# BT832A.net
KiCad netlist of a schematic drawn in EAGLE
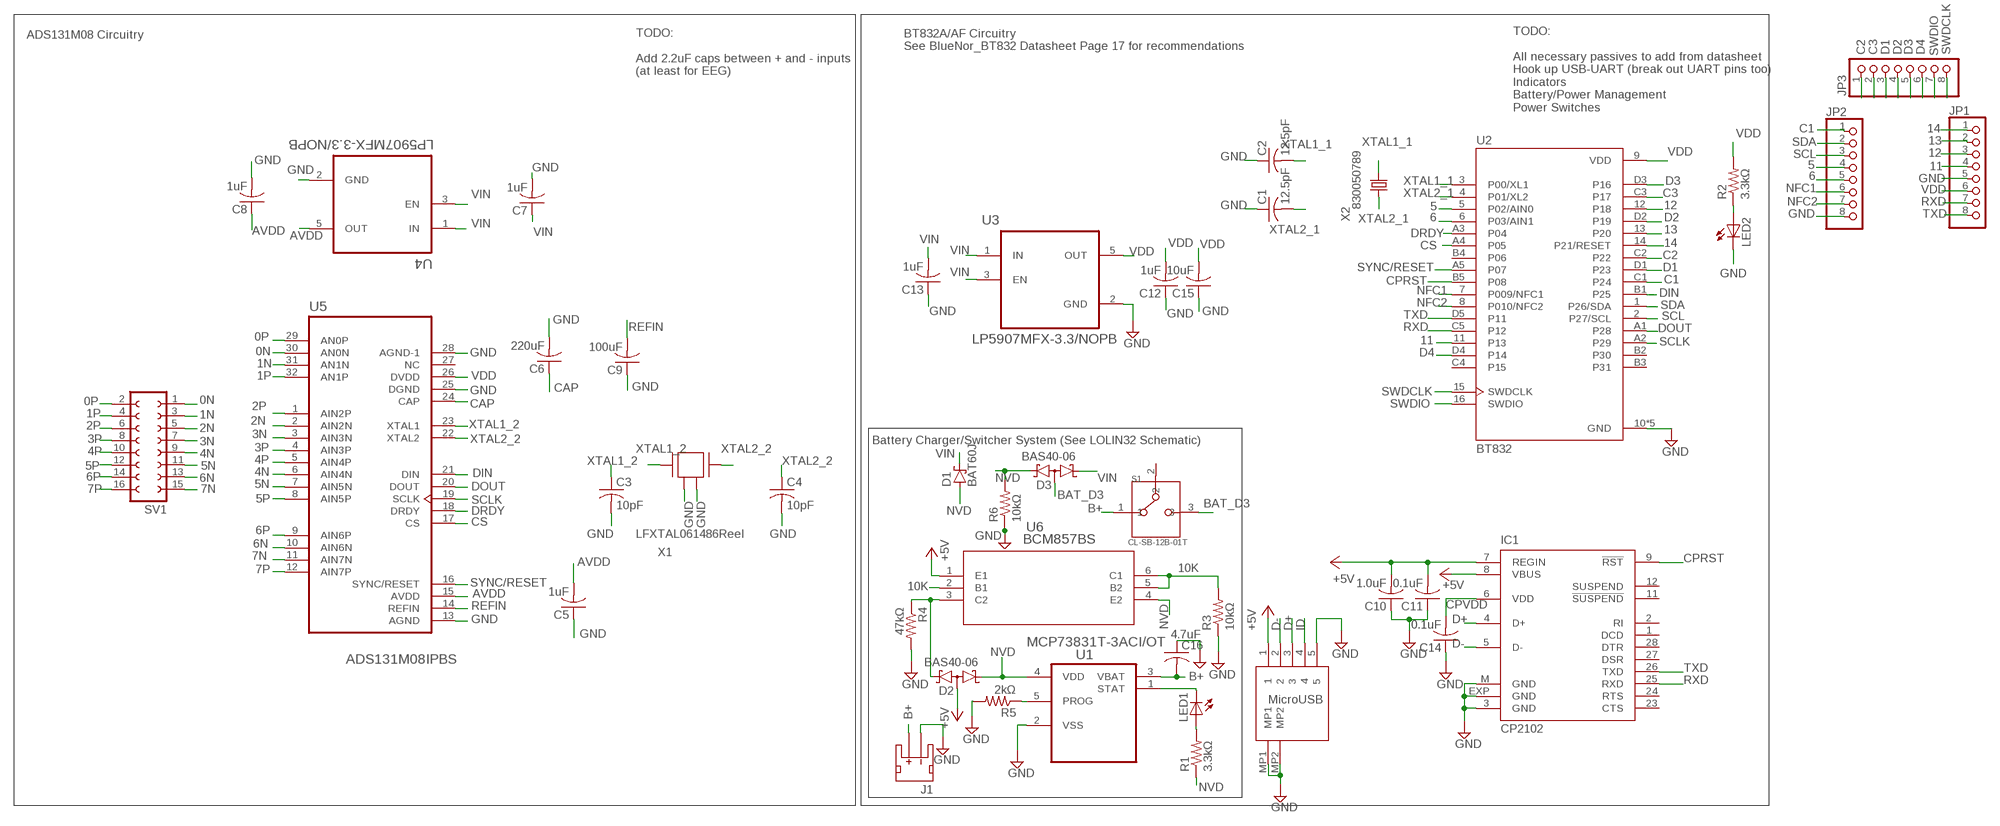
[diagram p0: schematic, sheet 1]

(export (version "E")
  (design (tool "Eeschema 10.0.6"))
  (components
    (comp (ref "C1")
      (value "12.5pF")
      (footprint "eagle-import:C0402")
      (libsource (lib "eagle-import") (part "adafruit_420_C-USC0402"))
    )
    (comp (ref "C2")
      (value "12.5pF")
      (footprint "eagle-import:C0402")
      (libsource (lib "eagle-import") (part "adafruit_420_C-USC0402"))
    )
    (comp (ref "C3")
      (value "10pF")
      (footprint "eagle-import:C0402")
      (libsource (lib "eagle-import") (part "adafruit_420_C-USC0402"))
    )
    (comp (ref "C4")
      (value "10pF")
      (footprint "eagle-import:C0402")
      (libsource (lib "eagle-import") (part "adafruit_420_C-USC0402"))
    )
    (comp (ref "C5")
      (value "1uF")
      (footprint "eagle-import:C0402")
      (libsource (lib "eagle-import") (part "C-USC0402"))
    )
    (comp (ref "C6")
      (value "220uF")
      (footprint "eagle-import:C0402")
      (libsource (lib "eagle-import") (part "C-USC0402"))
    )
    (comp (ref "C7")
      (value "1uF")
      (footprint "eagle-import:C0402")
      (libsource (lib "eagle-import") (part "C-USC0402"))
    )
    (comp (ref "C8")
      (value "1uF")
      (footprint "eagle-import:C0402")
      (libsource (lib "eagle-import") (part "C-USC0402"))
    )
    (comp (ref "C9")
      (value "100uF")
      (footprint "eagle-import:C0402")
      (libsource (lib "eagle-import") (part "C-USC0402"))
    )
    (comp (ref "C10")
      (value "1.0uF")
      (footprint "eagle-import:C0402")
      (libsource (lib "eagle-import") (part "adafruit_420_C-USC0402"))
    )
    (comp (ref "C11")
      (value "0.1uF")
      (footprint "eagle-import:C0402")
      (libsource (lib "eagle-import") (part "adafruit_420_C-USC0402"))
    )
    (comp (ref "C12")
      (value "1uF")
      (footprint "eagle-import:C0402")
      (libsource (lib "eagle-import") (part "C-USC0402"))
    )
    (comp (ref "C13")
      (value "1uF")
      (footprint "eagle-import:C0402")
      (libsource (lib "eagle-import") (part "C-USC0402"))
    )
    (comp (ref "C14")
      (value "0.1uF")
      (footprint "eagle-import:C0402")
      (libsource (lib "eagle-import") (part "adafruit_420_C-USC0402"))
    )
    (comp (ref "C15")
      (value "10uF")
      (footprint "eagle-import:C0402")
      (libsource (lib "eagle-import") (part "C-USC0402"))
    )
    (comp (ref "C16")
      (value "4.7uF")
      (footprint "eagle-import:C0402")
      (libsource (lib "eagle-import") (part "adafruit_420_C-USC0402"))
    )
    (comp (ref "D1")
      (value "BAT60J")
      (footprint "eagle-import:SOD323_ST")
      (libsource (lib "eagle-import") (part "BAT60J"))
    )
    (comp (ref "D2")
      (value "BAS40-06")
      (footprint "eagle-import:SOT23")
      (libsource (lib "eagle-import") (part "BAS40-06"))
    )
    (comp (ref "D3")
      (value "BAS40-06")
      (footprint "eagle-import:SOT23")
      (libsource (lib "eagle-import") (part "BAS40-06"))
    )
    (comp (ref "IC1")
      (value "CP2102")
      (footprint "eagle-import:MLP28")
      (fields (field (name "MF") "FARNELL") (field (name "MPN") "CP2102-GM"))
      (libsource (lib "eagle-import") (part "CP2102"))
    )
    (comp (ref "J1")
      (value "JST_2MM_MALE")
      (footprint "eagle-import:JST-2-SMD")
      (libsource (lib "eagle-import") (part "JST_2MM_MALE"))
    )
    (comp (ref "JP1")
      (value "PINHD-1X8CLEANBIG")
      (footprint "eagle-import:1X08-CLEANBIG")
      (libsource (lib "eagle-import") (part "PINHD-1X8CLEANBIG"))
    )
    (comp (ref "JP2")
      (value "PINHD-1X8CLEANBIG")
      (footprint "eagle-import:1X08-CLEANBIG")
      (libsource (lib "eagle-import") (part "PINHD-1X8CLEANBIG"))
    )
    (comp (ref "JP3")
      (value "PINHD-1X8CLEANBIG")
      (footprint "eagle-import:1X08-CLEANBIG")
      (libsource (lib "eagle-import") (part "PINHD-1X8CLEANBIG"))
    )
    (comp (ref "LED1")
      (value "LEDCHIP-LED0603")
      (footprint "eagle-import:CHIP-LED0603")
      (libsource (lib "eagle-import") (part "LEDCHIP-LED0603"))
    )
    (comp (ref "LED2")
      (value "LEDCHIP-LED0603")
      (footprint "eagle-import:CHIP-LED0603")
      (libsource (lib "eagle-import") (part "LEDCHIP-LED0603"))
    )
    (comp (ref "R1")
      (value "3.3kΩ")
      (footprint "eagle-import:R0402")
      (libsource (lib "eagle-import") (part "R-US_R0402"))
    )
    (comp (ref "R2")
      (value "3.3kΩ")
      (footprint "eagle-import:R0402")
      (libsource (lib "eagle-import") (part "R-US_R0402"))
    )
    (comp (ref "R3")
      (value "10kΩ")
      (footprint "eagle-import:R0402")
      (libsource (lib "eagle-import") (part "R-US_R0402"))
    )
    (comp (ref "R4")
      (value "47kΩ")
      (footprint "eagle-import:R0402")
      (libsource (lib "eagle-import") (part "R-US_R0402"))
    )
    (comp (ref "R5")
      (value "2kΩ")
      (footprint "eagle-import:R0402")
      (libsource (lib "eagle-import") (part "R-US_R0402"))
    )
    (comp (ref "R6")
      (value "10kΩ")
      (footprint "eagle-import:R0402")
      (libsource (lib "eagle-import") (part "R-US_R0402"))
    )
    (comp (ref "S1")
      (value "CL-SB-12B-01T")
      (footprint "eagle-import:CL-SB-12B")
      (fields (field (name "MF") "Nidec Copal"))
      (libsource (lib "eagle-import") (part "CL-SB-12B-01T"))
    )
    (comp (ref "SV1")
      (value "FE08-2")
      (footprint "eagle-import:FE08-2")
      (libsource (lib "eagle-import") (part "FE08-2"))
    )
    (comp (ref "U$1")
      (value "DX4R005JJ2R1800")
      (footprint "eagle-import:DX4R005JJ2R1800")
      (fields (field (name "MF") "JAE Electronics"))
      (libsource (lib "eagle-import") (part "DX4R005JJ2R1800"))
    )
    (comp (ref "U1")
      (value "MCP73831T-3ACI/OT")
      (footprint "eagle-import:SOT95P270X145-5N")
      (fields (field (name "MF") "Microchip"))
      (libsource (lib "eagle-import") (part "MCP73831T-3ACI/OT"))
    )
    (comp (ref "U2")
      (value "BT832")
      (footprint "eagle-import:BLEMODULE_BT832")
      (fields (field (name "MF") "Fanstel Corp."))
      (libsource (lib "eagle-import") (part "BT832"))
    )
    (comp (ref "U3")
      (value "LP5907MFX-3.3/NOPB")
      (footprint "eagle-import:SOT95P280X145-5N")
      (fields (field (name "MF") "Texas Instruments"))
      (libsource (lib "eagle-import") (part "LP5907MFX-3.3/NOPB"))
    )
    (comp (ref "U4")
      (value "LP5907MFX-3.3/NOPB")
      (footprint "eagle-import:SOT95P280X145-5N")
      (fields (field (name "MF") "Texas Instruments"))
      (libsource (lib "eagle-import") (part "LP5907MFX-3.3/NOPB"))
    )
    (comp (ref "U5")
      (value "ADS131M08IPBS")
      (footprint "eagle-import:QFP50P700X700X120-32N")
      (fields (field (name "MF") "Texas Instruments"))
      (libsource (lib "eagle-import") (part "ADS131M08IPBS"))
    )
    (comp (ref "U6")
      (value "BCM857BS")
      (footprint "eagle-import:SOT363_NEX")
      (fields (field (name "COPYRIGHT") "Copyright (C) 2016 Accelerated Designs. All rights reserved"))
      (libsource (lib "eagle-import") (part "BCM857BS"))
    )
    (comp (ref "X1")
      (value "ABM3B-8.000MHZ-B2-T")
      (footprint "eagle-import:ABM3B-8.000MHZ-B2-T")
      (fields
        (field (name "DIGIKEY_PART_NUMBER") "535-9720-2-ND")
        (field (name "MANUFACTURER") "Abracon LLC")
        (field (name "CREATED_BY") "PCBLayout.com")
      )
      (libsource (lib "eagle-import") (part "ABM3B-8.000MHZ-B2-T"))
    )
    (comp (ref "X2")
      (value "FC-12M")
      (footprint "eagle-import:FC-12M")
      (libsource (lib "eagle-import") (part "FC-12M"))
    )
  )
  (nets
    (net (code "1") (name "+5V") (class "Default")
      (node (ref "C10") (pin "2") (pinfunction "2_2") (pintype "passive"))
      (node (ref "C11") (pin "2") (pinfunction "2_2") (pintype "passive"))
      (node (ref "D2") (pin "3") (pinfunction "AA_3") (pintype "passive"))
      (node (ref "IC1") (pin "7") (pinfunction "REGIN_7") (pintype "passive"))
      (node (ref "IC1") (pin "8") (pinfunction "VBUS_8") (pintype "input"))
      (node (ref "U$1") (pin "1") (pinfunction "1_1") (pintype "bidirectional"))
      (node (ref "U6") (pin "1") (pinfunction "E1_1") (pintype "passive"))
    )
    (net (code "2") (name "0N") (class "Default")
      (node (ref "SV1") (pin "1") (pinfunction "1_1") (pintype "passive"))
      (node (ref "U5") (pin "30") (pinfunction "AN0N_30") (pintype "bidirectional"))
    )
    (net (code "3") (name "0P") (class "Default")
      (node (ref "SV1") (pin "2") (pinfunction "2_2") (pintype "passive"))
      (node (ref "U5") (pin "29") (pinfunction "AN0P_29") (pintype "bidirectional"))
    )
    (net (code "4") (name "1N") (class "Default")
      (node (ref "SV1") (pin "3") (pinfunction "3_3") (pintype "passive"))
      (node (ref "U5") (pin "31") (pinfunction "AN1N_31") (pintype "bidirectional"))
    )
    (net (code "5") (name "1P") (class "Default")
      (node (ref "SV1") (pin "4") (pinfunction "4_4") (pintype "passive"))
      (node (ref "U5") (pin "32") (pinfunction "AN1P_32") (pintype "bidirectional"))
    )
    (net (code "6") (name "2N") (class "Default")
      (node (ref "SV1") (pin "5") (pinfunction "5_5") (pintype "passive"))
      (node (ref "U5") (pin "2") (pinfunction "AIN2N_2") (pintype "input"))
    )
    (net (code "7") (name "2P") (class "Default")
      (node (ref "SV1") (pin "6") (pinfunction "6_6") (pintype "passive"))
      (node (ref "U5") (pin "1") (pinfunction "AIN2P_1") (pintype "input"))
    )
    (net (code "8") (name "3N") (class "Default")
      (node (ref "SV1") (pin "7") (pinfunction "7_7") (pintype "passive"))
      (node (ref "U5") (pin "3") (pinfunction "AIN3N_3") (pintype "input"))
    )
    (net (code "9") (name "3P") (class "Default")
      (node (ref "SV1") (pin "8") (pinfunction "8_8") (pintype "passive"))
      (node (ref "U5") (pin "4") (pinfunction "AIN3P_4") (pintype "input"))
    )
    (net (code "10") (name "4N") (class "Default")
      (node (ref "SV1") (pin "9") (pinfunction "9_9") (pintype "passive"))
      (node (ref "U5") (pin "6") (pinfunction "AIN4N_6") (pintype "input"))
    )
    (net (code "11") (name "4P") (class "Default")
      (node (ref "SV1") (pin "10") (pinfunction "10_10") (pintype "passive"))
      (node (ref "U5") (pin "5") (pinfunction "AIN4P_5") (pintype "input"))
    )
    (net (code "12") (name "5") (class "Default")
      (node (ref "JP2") (pin "4") (pinfunction "4_4") (pintype "passive"))
      (node (ref "U2") (pin "5") (pinfunction "P02/AIN0_5") (pintype "bidirectional"))
    )
    (net (code "13") (name "5N") (class "Default")
      (node (ref "SV1") (pin "11") (pinfunction "11_11") (pintype "passive"))
      (node (ref "U5") (pin "7") (pinfunction "AIN5N_7") (pintype "input"))
    )
    (net (code "14") (name "5P") (class "Default")
      (node (ref "SV1") (pin "12") (pinfunction "12_12") (pintype "passive"))
      (node (ref "U5") (pin "8") (pinfunction "AIN5P_8") (pintype "input"))
    )
    (net (code "15") (name "6") (class "Default")
      (node (ref "JP2") (pin "5") (pinfunction "5_5") (pintype "passive"))
      (node (ref "U2") (pin "6") (pinfunction "P03/AIN1_6") (pintype "bidirectional"))
    )
    (net (code "16") (name "6N") (class "Default")
      (node (ref "SV1") (pin "13") (pinfunction "13_13") (pintype "passive"))
      (node (ref "U5") (pin "10") (pinfunction "AIN6N_10") (pintype "input"))
    )
    (net (code "17") (name "6P") (class "Default")
      (node (ref "SV1") (pin "14") (pinfunction "14_14") (pintype "passive"))
      (node (ref "U5") (pin "9") (pinfunction "AIN6P_9") (pintype "input"))
    )
    (net (code "18") (name "7N") (class "Default")
      (node (ref "SV1") (pin "15") (pinfunction "15_15") (pintype "passive"))
      (node (ref "U5") (pin "11") (pinfunction "AIN7N_11") (pintype "input"))
    )
    (net (code "19") (name "7P") (class "Default")
      (node (ref "SV1") (pin "16") (pinfunction "16_16") (pintype "passive"))
      (node (ref "U5") (pin "12") (pinfunction "AIN7P_12") (pintype "input"))
    )
    (net (code "20") (name "10K") (class "Default")
      (node (ref "R3") (pin "2") (pinfunction "2_2") (pintype "passive"))
      (node (ref "U6") (pin "2") (pinfunction "B1_2") (pintype "passive"))
      (node (ref "U6") (pin "5") (pinfunction "B2_5") (pintype "passive"))
      (node (ref "U6") (pin "6") (pinfunction "C1_6") (pintype "passive"))
    )
    (net (code "21") (name "11") (class "Default")
      (node (ref "JP1") (pin "4") (pinfunction "4_4") (pintype "passive"))
      (node (ref "U2") (pin "11") (pinfunction "P13_11") (pintype "bidirectional"))
    )
    (net (code "22") (name "12") (class "Default")
      (node (ref "JP1") (pin "3") (pinfunction "3_3") (pintype "passive"))
      (node (ref "U2") (pin "12") (pinfunction "P18_12") (pintype "bidirectional"))
    )
    (net (code "23") (name "13") (class "Default")
      (node (ref "JP1") (pin "2") (pinfunction "2_2") (pintype "passive"))
      (node (ref "U2") (pin "13") (pinfunction "P20_13") (pintype "bidirectional"))
    )
    (net (code "24") (name "14") (class "Default")
      (node (ref "JP1") (pin "1") (pinfunction "1_1") (pintype "passive"))
      (node (ref "U2") (pin "14") (pinfunction "P21/RESET_14") (pintype "bidirectional"))
    )
    (net (code "25") (name "AVDD") (class "Default")
      (node (ref "C5") (pin "2") (pinfunction "2_2") (pintype "passive"))
      (node (ref "C8") (pin "1") (pinfunction "1_1") (pintype "passive"))
      (node (ref "U4") (pin "5") (pinfunction "OUT_5") (pintype "output"))
      (node (ref "U5") (pin "15") (pinfunction "AVDD_15") (pintype "power_in"))
    )
    (net (code "26") (name "B+") (class "Default")
      (node (ref "C16") (pin "2") (pinfunction "2_2") (pintype "passive"))
      (node (ref "J1") (pin "2") (pinfunction "+_2") (pintype "bidirectional"))
      (node (ref "S1") (pin "1") (pinfunction "1_1") (pintype "bidirectional"))
      (node (ref "U1") (pin "3") (pinfunction "VBAT_3") (pintype "power_in"))
    )
    (net (code "27") (name "BAT_D3") (class "Default")
      (node (ref "D3") (pin "3") (pinfunction "AA_3") (pintype "passive"))
      (node (ref "S1") (pin "3") (pinfunction "3_3") (pintype "bidirectional"))
    )
    (net (code "28") (name "C1") (class "Default")
      (node (ref "JP2") (pin "1") (pinfunction "1_1") (pintype "passive"))
      (node (ref "U2") (pin "C1") (pinfunction "P24_C1") (pintype "bidirectional"))
    )
    (net (code "29") (name "C2") (class "Default")
      (node (ref "JP3") (pin "1") (pinfunction "1_1") (pintype "passive"))
      (node (ref "U2") (pin "C2") (pinfunction "P22_C2") (pintype "bidirectional"))
    )
    (net (code "30") (name "C3") (class "Default")
      (node (ref "JP3") (pin "2") (pinfunction "2_2") (pintype "passive"))
      (node (ref "U2") (pin "C3") (pinfunction "P17_C3") (pintype "bidirectional"))
    )
    (net (code "31") (name "CAP") (class "Default")
      (node (ref "C6") (pin "1") (pinfunction "1_1") (pintype "passive"))
      (node (ref "U5") (pin "24") (pinfunction "CAP_24") (pintype "bidirectional"))
    )
    (net (code "32") (name "CPRST") (class "Default")
      (node (ref "IC1") (pin "9") (pinfunction "~{RST}_9") (pintype "bidirectional"))
      (node (ref "U2") (pin "B5") (pinfunction "P08_B5") (pintype "bidirectional"))
    )
    (net (code "33") (name "CPVDD") (class "Default")
      (node (ref "C14") (pin "2") (pinfunction "2_2") (pintype "passive"))
      (node (ref "IC1") (pin "6") (pinfunction "VDD_6") (pintype "power_in"))
    )
    (net (code "34") (name "CS") (class "Default")
      (node (ref "U2") (pin "A4") (pinfunction "P05_A4") (pintype "bidirectional"))
      (node (ref "U5") (pin "17") (pinfunction "CS_17") (pintype "bidirectional"))
    )
    (net (code "35") (name "D+") (class "Default")
      (node (ref "IC1") (pin "4") (pinfunction "D+_4") (pintype "bidirectional"))
      (node (ref "U$1") (pin "3") (pinfunction "3_3") (pintype "bidirectional"))
    )
    (net (code "36") (name "D-") (class "Default")
      (node (ref "IC1") (pin "5") (pinfunction "D-_5") (pintype "bidirectional"))
      (node (ref "U$1") (pin "2") (pinfunction "2_2") (pintype "bidirectional"))
    )
    (net (code "37") (name "D1") (class "Default")
      (node (ref "JP3") (pin "3") (pinfunction "3_3") (pintype "passive"))
      (node (ref "U2") (pin "D1") (pinfunction "P23_D1") (pintype "bidirectional"))
    )
    (net (code "38") (name "D2") (class "Default")
      (node (ref "JP3") (pin "4") (pinfunction "4_4") (pintype "passive"))
      (node (ref "U2") (pin "D2") (pinfunction "P19_D2") (pintype "bidirectional"))
    )
    (net (code "39") (name "D3") (class "Default")
      (node (ref "JP3") (pin "5") (pinfunction "5_5") (pintype "passive"))
      (node (ref "U2") (pin "D3") (pinfunction "P16_D3") (pintype "bidirectional"))
    )
    (net (code "40") (name "D4") (class "Default")
      (node (ref "JP3") (pin "6") (pinfunction "6_6") (pintype "passive"))
      (node (ref "U2") (pin "D4") (pinfunction "P14_D4") (pintype "bidirectional"))
    )
    (net (code "41") (name "DIN") (class "Default")
      (node (ref "U2") (pin "B1") (pinfunction "P25_B1") (pintype "bidirectional"))
      (node (ref "U5") (pin "21") (pinfunction "DIN_21") (pintype "input"))
    )
    (net (code "42") (name "DOUT") (class "Default")
      (node (ref "U2") (pin "A1") (pinfunction "P28_A1") (pintype "bidirectional"))
      (node (ref "U5") (pin "20") (pinfunction "DOUT_20") (pintype "output"))
    )
    (net (code "43") (name "DRDY") (class "Default")
      (node (ref "U2") (pin "A3") (pinfunction "P04_A3") (pintype "bidirectional"))
      (node (ref "U5") (pin "18") (pinfunction "DRDY_18") (pintype "output"))
    )
    (net (code "44") (name "GND") (class "Default")
      (node (ref "C1") (pin "1") (pinfunction "1_1") (pintype "passive"))
      (node (ref "C10") (pin "1") (pinfunction "1_1") (pintype "passive"))
      (node (ref "C11") (pin "1") (pinfunction "1_1") (pintype "passive"))
      (node (ref "C12") (pin "1") (pinfunction "1_1") (pintype "passive"))
      (node (ref "C13") (pin "1") (pinfunction "1_1") (pintype "passive"))
      (node (ref "C14") (pin "1") (pinfunction "1_1") (pintype "passive"))
      (node (ref "C15") (pin "1") (pinfunction "1_1") (pintype "passive"))
      (node (ref "C16") (pin "1") (pinfunction "1_1") (pintype "passive"))
      (node (ref "C2") (pin "1") (pinfunction "1_1") (pintype "passive"))
      (node (ref "C3") (pin "2") (pinfunction "2_2") (pintype "passive"))
      (node (ref "C4") (pin "2") (pinfunction "2_2") (pintype "passive"))
      (node (ref "C5") (pin "1") (pinfunction "1_1") (pintype "passive"))
      (node (ref "C6") (pin "2") (pinfunction "2_2") (pintype "passive"))
      (node (ref "C7") (pin "2") (pinfunction "2_2") (pintype "passive"))
      (node (ref "C8") (pin "2") (pinfunction "2_2") (pintype "passive"))
      (node (ref "C9") (pin "1") (pinfunction "1_1") (pintype "passive"))
      (node (ref "IC1") (pin "3") (pinfunction "GND_3") (pintype "power_in"))
      (node (ref "IC1") (pin "EXP") (pinfunction "GND_EXP") (pintype "power_in"))
      (node (ref "IC1") (pin "M") (pinfunction "GND_M") (pintype "power_in"))
      (node (ref "J1") (pin "1") (pinfunction "-_1") (pintype "bidirectional"))
      (node (ref "JP1") (pin "5") (pinfunction "5_5") (pintype "passive"))
      (node (ref "JP2") (pin "8") (pinfunction "8_8") (pintype "passive"))
      (node (ref "LED2") (pin "C") (pinfunction "C_C") (pintype "passive"))
      (node (ref "R3") (pin "1") (pinfunction "1_1") (pintype "passive"))
      (node (ref "R4") (pin "2") (pinfunction "2_2") (pintype "passive"))
      (node (ref "R5") (pin "2") (pinfunction "2_2") (pintype "passive"))
      (node (ref "R6") (pin "1") (pinfunction "1_1") (pintype "passive"))
      (node (ref "U$1") (pin "5") (pinfunction "5_5") (pintype "bidirectional"))
      (node (ref "U$1") (pin "MP1") (pinfunction "MP1_MP1") (pintype "bidirectional"))
      (node (ref "U$1") (pin "MP2") (pinfunction "MP2_MP2") (pintype "bidirectional"))
      (node (ref "U1") (pin "2") (pinfunction "VSS_2") (pintype "power_in"))
      (node (ref "U2") (pin "10") (pinfunction "GND_10") (pintype "power_in"))
      (node (ref "U2") (pin "A0") (pinfunction "GND_A0") (pintype "power_in"))
      (node (ref "U2") (pin "B0") (pinfunction "GND_B0") (pintype "power_in"))
      (node (ref "U2") (pin "C0") (pinfunction "GND_C0") (pintype "power_in"))
      (node (ref "U2") (pin "D0") (pinfunction "GND_D0") (pintype "power_in"))
      (node (ref "U3") (pin "2") (pinfunction "GND_2") (pintype "power_in"))
      (node (ref "U4") (pin "2") (pinfunction "GND_2") (pintype "power_in"))
      (node (ref "U5") (pin "13") (pinfunction "AGND_13") (pintype "power_in"))
      (node (ref "U5") (pin "25") (pinfunction "DGND_25") (pintype "power_in"))
      (node (ref "U5") (pin "28") (pinfunction "AGND-1_28") (pintype "power_in"))
      (node (ref "X1") (pin "2") (pinfunction "2_2") (pintype "passive"))
      (node (ref "X1") (pin "4") (pinfunction "4_4") (pintype "passive"))
    )
    (net (code "45") (name "ID") (class "Default")
      (node (ref "U$1") (pin "4") (pinfunction "4_4") (pintype "bidirectional"))
    )
    (net (code "46") (name "NFC1") (class "Default")
      (node (ref "JP2") (pin "6") (pinfunction "6_6") (pintype "passive"))
      (node (ref "U2") (pin "7") (pinfunction "P009/NFC1_7") (pintype "bidirectional"))
    )
    (net (code "47") (name "NFC2") (class "Default")
      (node (ref "JP2") (pin "7") (pinfunction "7_7") (pintype "passive"))
      (node (ref "U2") (pin "8") (pinfunction "P010/NFC2_8") (pintype "bidirectional"))
    )
    (net (code "48") (name "NVD") (class "Default")
      (node (ref "D1") (pin "A") (pinfunction "A_A") (pintype "passive"))
      (node (ref "D2") (pin "1") (pinfunction "K1_1") (pintype "passive"))
      (node (ref "D3") (pin "2") (pinfunction "K2_2") (pintype "passive"))
      (node (ref "R1") (pin "1") (pinfunction "1_1") (pintype "passive"))
      (node (ref "R6") (pin "2") (pinfunction "2_2") (pintype "passive"))
      (node (ref "U1") (pin "4") (pinfunction "VDD_4") (pintype "power_in"))
      (node (ref "U6") (pin "4") (pinfunction "E2_4") (pintype "passive"))
    )
    (net (code "49") (name "Net-(D2-K2)") (class "Default")
      (node (ref "D2") (pin "2") (pinfunction "K2_2") (pintype "passive"))
      (node (ref "R4") (pin "1") (pinfunction "1_1") (pintype "passive"))
      (node (ref "U6") (pin "3") (pinfunction "C2_3") (pintype "passive"))
    )
    (net (code "50") (name "Net-(LED1-PadA)") (class "Default")
      (node (ref "LED1") (pin "A") (pinfunction "A_A") (pintype "passive"))
      (node (ref "R1") (pin "2") (pinfunction "2_2") (pintype "passive"))
    )
    (net (code "51") (name "Net-(LED2-PadA)") (class "Default")
      (node (ref "LED2") (pin "A") (pinfunction "A_A") (pintype "passive"))
      (node (ref "R2") (pin "1") (pinfunction "1_1") (pintype "passive"))
    )
    (net (code "52") (name "Net-(U1-PROG)") (class "Default")
      (node (ref "R5") (pin "1") (pinfunction "1_1") (pintype "passive"))
      (node (ref "U1") (pin "5") (pinfunction "PROG_5") (pintype "input"))
    )
    (net (code "53") (name "Net-(U1-STAT)") (class "Default")
      (node (ref "LED1") (pin "C") (pinfunction "C_C") (pintype "passive"))
      (node (ref "U1") (pin "1") (pinfunction "STAT_1") (pintype "output"))
    )
    (net (code "54") (name "REFIN") (class "Default")
      (node (ref "C9") (pin "2") (pinfunction "2_2") (pintype "passive"))
      (node (ref "U5") (pin "14") (pinfunction "REFIN_14") (pintype "input"))
    )
    (net (code "55") (name "RXD") (class "Default")
      (node (ref "IC1") (pin "25") (pinfunction "RXD_25") (pintype "input"))
      (node (ref "JP1") (pin "7") (pinfunction "7_7") (pintype "passive"))
      (node (ref "U2") (pin "C5") (pinfunction "P12_C5") (pintype "bidirectional"))
    )
    (net (code "56") (name "SCL") (class "Default")
      (node (ref "JP2") (pin "3") (pinfunction "3_3") (pintype "passive"))
      (node (ref "U2") (pin "2") (pinfunction "P27/SCL_2") (pintype "bidirectional"))
    )
    (net (code "57") (name "SCLK") (class "Default")
      (node (ref "U2") (pin "A2") (pinfunction "P29_A2") (pintype "bidirectional"))
      (node (ref "U5") (pin "19") (pinfunction "SCLK_19") (pintype "input"))
    )
    (net (code "58") (name "SDA") (class "Default")
      (node (ref "JP2") (pin "2") (pinfunction "2_2") (pintype "passive"))
      (node (ref "U2") (pin "1") (pinfunction "P26/SDA_1") (pintype "bidirectional"))
    )
    (net (code "59") (name "SWDCLK") (class "Default")
      (node (ref "JP3") (pin "8") (pinfunction "8_8") (pintype "passive"))
      (node (ref "U2") (pin "15") (pinfunction "SWDCLK_15") (pintype "input"))
    )
    (net (code "60") (name "SWDIO") (class "Default")
      (node (ref "JP3") (pin "7") (pinfunction "7_7") (pintype "passive"))
      (node (ref "U2") (pin "16") (pinfunction "SWDIO_16") (pintype "bidirectional"))
    )
    (net (code "61") (name "SYNC{slash}RESET") (class "Default")
      (node (ref "U2") (pin "A5") (pinfunction "P07_A5") (pintype "bidirectional"))
      (node (ref "U5") (pin "16") (pinfunction "SYNC/RESET_16") (pintype "bidirectional"))
    )
    (net (code "62") (name "TXD") (class "Default")
      (node (ref "IC1") (pin "26") (pinfunction "TXD_26") (pintype "output"))
      (node (ref "JP1") (pin "8") (pinfunction "8_8") (pintype "passive"))
      (node (ref "U2") (pin "D5") (pinfunction "P11_D5") (pintype "bidirectional"))
    )
    (net (code "63") (name "VDD") (class "Default")
      (node (ref "C12") (pin "2") (pinfunction "2_2") (pintype "passive"))
      (node (ref "C15") (pin "2") (pinfunction "2_2") (pintype "passive"))
      (node (ref "JP1") (pin "6") (pinfunction "6_6") (pintype "passive"))
      (node (ref "R2") (pin "2") (pinfunction "2_2") (pintype "passive"))
      (node (ref "U2") (pin "9") (pinfunction "VDD_9") (pintype "power_in"))
      (node (ref "U3") (pin "5") (pinfunction "OUT_5") (pintype "output"))
      (node (ref "U5") (pin "26") (pinfunction "DVDD_26") (pintype "power_in"))
    )
    (net (code "64") (name "VIN") (class "Default")
      (node (ref "C13") (pin "2") (pinfunction "2_2") (pintype "passive"))
      (node (ref "C7") (pin "1") (pinfunction "1_1") (pintype "passive"))
      (node (ref "D1") (pin "C") (pinfunction "C_C") (pintype "passive"))
      (node (ref "D3") (pin "1") (pinfunction "K1_1") (pintype "passive"))
      (node (ref "U3") (pin "1") (pinfunction "IN_1") (pintype "input"))
      (node (ref "U3") (pin "3") (pinfunction "EN_3") (pintype "input"))
      (node (ref "U4") (pin "1") (pinfunction "IN_1") (pintype "input"))
      (node (ref "U4") (pin "3") (pinfunction "EN_3") (pintype "input"))
    )
    (net (code "65") (name "XTAL1_1") (class "Default")
      (node (ref "C2") (pin "2") (pinfunction "2_2") (pintype "passive"))
      (node (ref "U2") (pin "3") (pinfunction "P00/XL1_3") (pintype "bidirectional"))
      (node (ref "X2") (pin "2") (pinfunction "2_2") (pintype "passive"))
    )
    (net (code "66") (name "XTAL1_2") (class "Default")
      (node (ref "C3") (pin "1") (pinfunction "1_1") (pintype "passive"))
      (node (ref "U5") (pin "23") (pinfunction "XTAL1_23") (pintype "bidirectional"))
      (node (ref "X1") (pin "1") (pinfunction "1_1") (pintype "passive"))
    )
    (net (code "67") (name "XTAL2_1") (class "Default")
      (node (ref "C1") (pin "2") (pinfunction "2_2") (pintype "passive"))
      (node (ref "U2") (pin "4") (pinfunction "P01/XL2_4") (pintype "bidirectional"))
      (node (ref "X2") (pin "1") (pinfunction "1_1") (pintype "passive"))
    )
    (net (code "68") (name "XTAL2_2") (class "Default")
      (node (ref "C4") (pin "1") (pinfunction "1_1") (pintype "passive"))
      (node (ref "U5") (pin "22") (pinfunction "XTAL2_22") (pintype "bidirectional"))
      (node (ref "X1") (pin "3") (pinfunction "3_3") (pintype "passive"))
    )
    (net (code "69") (name "unconnected-(IC1-CTS-Pad23)") (class "Default")
      (node (ref "IC1") (pin "23") (pinfunction "CTS_23") (pintype "input"))
    )
    (net (code "70") (name "unconnected-(IC1-DCD-Pad1)") (class "Default")
      (node (ref "IC1") (pin "1") (pinfunction "DCD_1") (pintype "input"))
    )
    (net (code "71") (name "unconnected-(IC1-DSR-Pad27)") (class "Default")
      (node (ref "IC1") (pin "27") (pinfunction "DSR_27") (pintype "input"))
    )
    (net (code "72") (name "unconnected-(IC1-DTR-Pad28)") (class "Default")
      (node (ref "IC1") (pin "28") (pinfunction "DTR_28") (pintype "output"))
    )
    (net (code "73") (name "unconnected-(IC1-RI-Pad2)") (class "Default")
      (node (ref "IC1") (pin "2") (pinfunction "RI_2") (pintype "input"))
    )
    (net (code "74") (name "unconnected-(IC1-RTS-Pad24)") (class "Default")
      (node (ref "IC1") (pin "24") (pinfunction "RTS_24") (pintype "output"))
    )
    (net (code "75") (name "unconnected-(IC1-SUSPEND-Pad12)") (class "Default")
      (node (ref "IC1") (pin "12") (pinfunction "SUSPEND_12") (pintype "output"))
    )
    (net (code "76") (name "unconnected-(IC1-~{SUSPEND}-Pad11)") (class "Default")
      (node (ref "IC1") (pin "11") (pinfunction "~{SUSPEND}_11") (pintype "output"))
    )
    (net (code "77") (name "unconnected-(J1-PAD1-PadNC1)") (class "Default")
      (node (ref "J1") (pin "NC1") (pinfunction "PAD1_NC1") (pintype "bidirectional"))
    )
    (net (code "78") (name "unconnected-(J1-PAD2-PadNC2)") (class "Default")
      (node (ref "J1") (pin "NC2") (pinfunction "PAD2_NC2") (pintype "bidirectional"))
    )
    (net (code "79") (name "unconnected-(S1-Pad2)") (class "Default")
      (node (ref "S1") (pin "2") (pinfunction "2_2") (pintype "bidirectional"))
    )
    (net (code "80") (name "unconnected-(U2-P06-PadB4)") (class "Default")
      (node (ref "U2") (pin "B4") (pinfunction "P06_B4") (pintype "bidirectional"))
    )
    (net (code "81") (name "unconnected-(U2-P15-PadC4)") (class "Default")
      (node (ref "U2") (pin "C4") (pinfunction "P15_C4") (pintype "bidirectional"))
    )
    (net (code "82") (name "unconnected-(U2-P30-PadB2)") (class "Default")
      (node (ref "U2") (pin "B2") (pinfunction "P30_B2") (pintype "bidirectional"))
    )
    (net (code "83") (name "unconnected-(U2-P31-PadB3)") (class "Default")
      (node (ref "U2") (pin "B3") (pinfunction "P31_B3") (pintype "bidirectional"))
    )
    (net (code "84") (name "unconnected-(U5-NC-Pad27)") (class "Default")
      (node (ref "U5") (pin "27") (pinfunction "NC_27") (pintype "bidirectional"))
    )
  )
)
